# SuperLogger_widewithESPSIM800bevorroutin.net
KiCad netlist of a schematic drawn in EAGLE
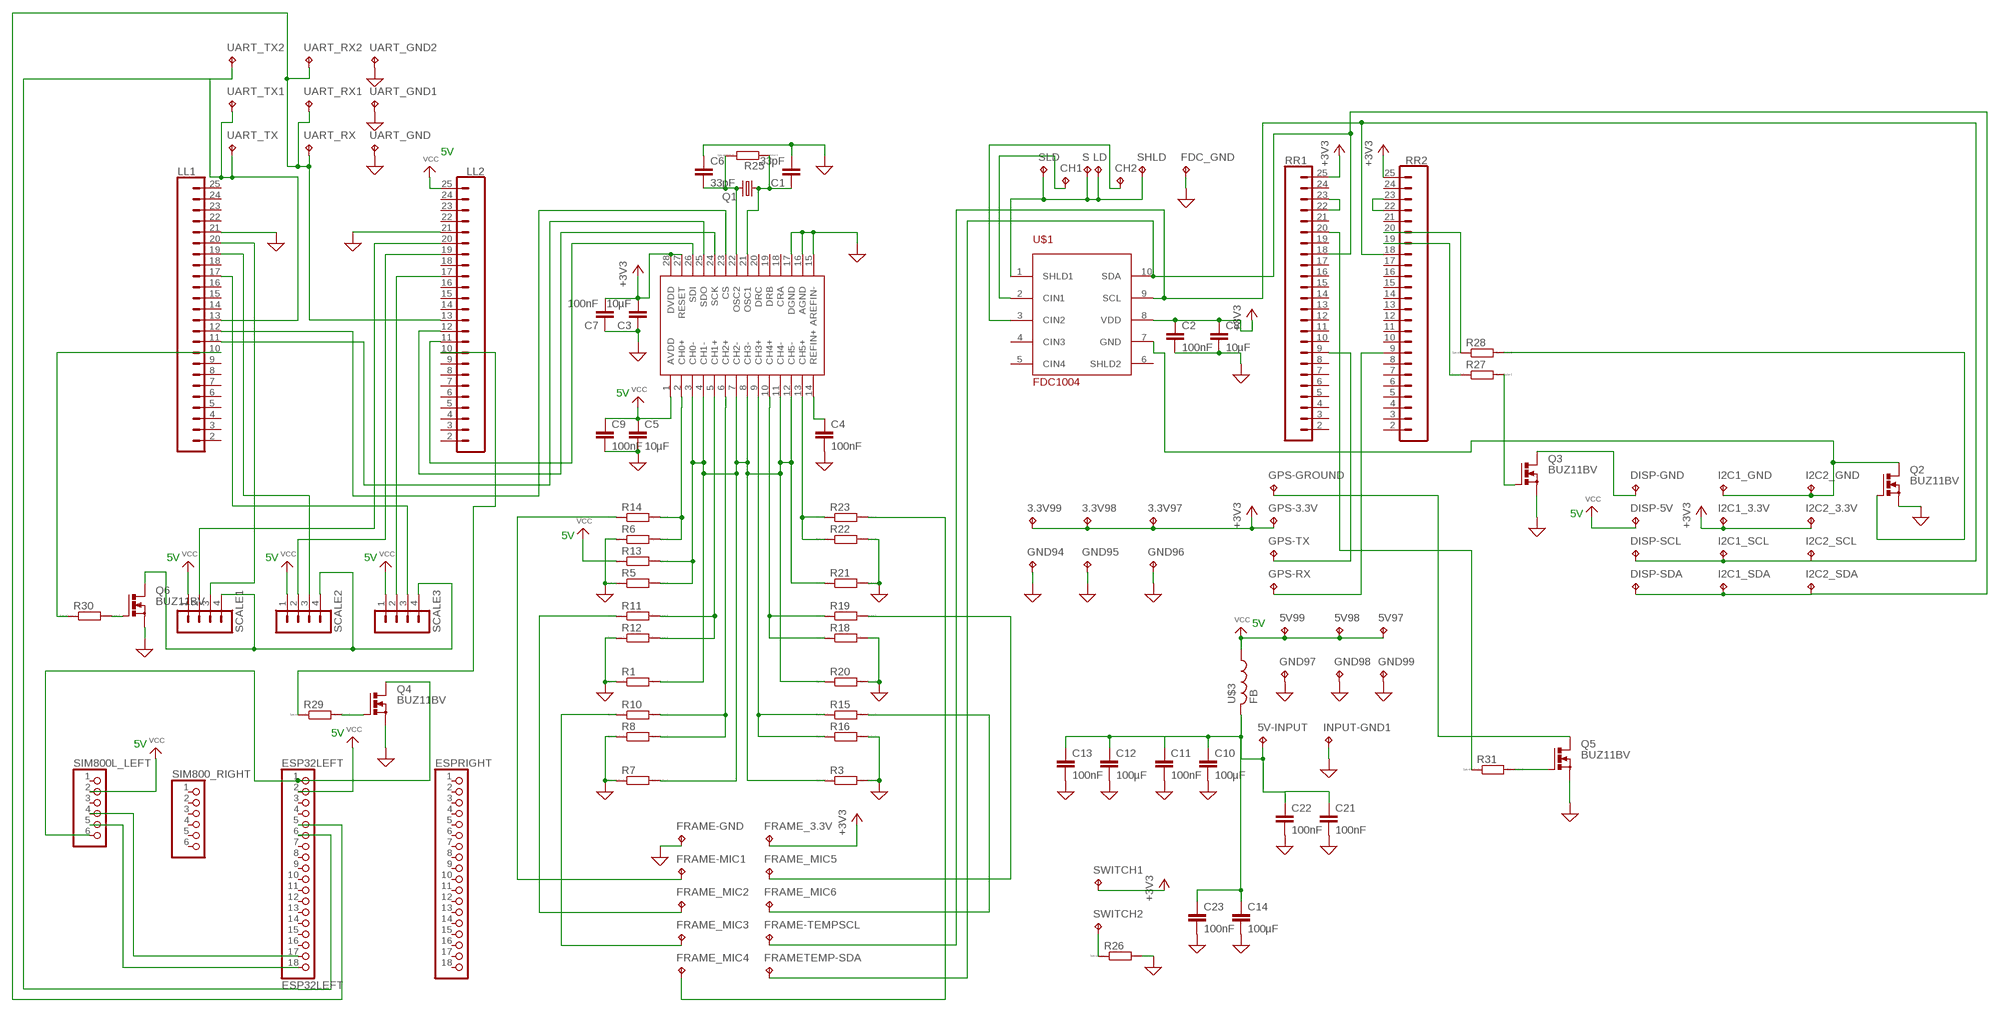
[diagram p0: schematic, sheet 1]

(export (version "E")
  (design (tool "Eeschema 10.0.6"))
  (components
    (comp (ref "3.3V97")
      (value "ground")
      (footprint "eagle-import:P1-13Y")
      (libsource (lib "eagle-import") (part "TPPAD1-13Y"))
    )
    (comp (ref "3.3V98")
      (value "ground")
      (footprint "eagle-import:P1-13Y")
      (libsource (lib "eagle-import") (part "TPPAD1-13Y"))
    )
    (comp (ref "3.3V99")
      (value "ground")
      (footprint "eagle-import:P1-13Y")
      (libsource (lib "eagle-import") (part "TPPAD1-13Y"))
    )
    (comp (ref "5V-INPUT")
      (value "ground")
      (footprint "eagle-import:P1-13Y")
      (libsource (lib "eagle-import") (part "TPPAD1-13Y"))
    )
    (comp (ref "5V97")
      (value "ground")
      (footprint "eagle-import:P1-13Y")
      (libsource (lib "eagle-import") (part "TPPAD1-13Y"))
    )
    (comp (ref "5V98")
      (value "ground")
      (footprint "eagle-import:P1-13Y")
      (libsource (lib "eagle-import") (part "TPPAD1-13Y"))
    )
    (comp (ref "5V99")
      (value "ground")
      (footprint "eagle-import:P1-13Y")
      (libsource (lib "eagle-import") (part "TPPAD1-13Y"))
    )
    (comp (ref "C1")
      (value "33pF")
      (footprint "eagle-import:C5B3")
      (libsource (lib "eagle-import") (part "C5/3"))
    )
    (comp (ref "C2")
      (value "100nF")
      (footprint "eagle-import:C5B3")
      (libsource (lib "eagle-import") (part "C5/3"))
    )
    (comp (ref "C3")
      (value "10µF")
      (footprint "eagle-import:C5B3")
      (libsource (lib "eagle-import") (part "C5/3"))
    )
    (comp (ref "C4")
      (value "100nF")
      (footprint "eagle-import:C5B3")
      (libsource (lib "eagle-import") (part "C5/3"))
    )
    (comp (ref "C5")
      (value "10µF")
      (footprint "eagle-import:C5B3")
      (libsource (lib "eagle-import") (part "C5/3"))
    )
    (comp (ref "C6")
      (value "33pF")
      (footprint "eagle-import:C5B3")
      (libsource (lib "eagle-import") (part "C5/3"))
    )
    (comp (ref "C7")
      (value "100nF")
      (footprint "eagle-import:C5B3")
      (libsource (lib "eagle-import") (part "C5/3"))
    )
    (comp (ref "C8")
      (value "10µF")
      (footprint "eagle-import:C5B3")
      (libsource (lib "eagle-import") (part "C5/3"))
    )
    (comp (ref "C9")
      (value "100nF")
      (footprint "eagle-import:C5B3")
      (libsource (lib "eagle-import") (part "C5/3"))
    )
    (comp (ref "C10")
      (value "100µF")
      (footprint "eagle-import:C5B3")
      (libsource (lib "eagle-import") (part "C5/3"))
    )
    (comp (ref "C11")
      (value "100nF")
      (footprint "eagle-import:C5B3")
      (libsource (lib "eagle-import") (part "C5/3"))
    )
    (comp (ref "C12")
      (value "100µF")
      (footprint "eagle-import:C5B3")
      (libsource (lib "eagle-import") (part "C5/3"))
    )
    (comp (ref "C13")
      (value "100nF")
      (footprint "eagle-import:C5B3")
      (libsource (lib "eagle-import") (part "C5/3"))
    )
    (comp (ref "C14")
      (value "100µF")
      (footprint "eagle-import:C5B3")
      (libsource (lib "eagle-import") (part "C5/3"))
    )
    (comp (ref "C21")
      (value "100nF")
      (footprint "eagle-import:C5B3")
      (libsource (lib "eagle-import") (part "C5/3"))
    )
    (comp (ref "C22")
      (value "100nF")
      (footprint "eagle-import:C5B3")
      (libsource (lib "eagle-import") (part "C5/3"))
    )
    (comp (ref "C23")
      (value "100nF")
      (footprint "eagle-import:C5B3")
      (libsource (lib "eagle-import") (part "C5/3"))
    )
    (comp (ref "CH1")
      (value "ground")
      (footprint "eagle-import:P1-13Y")
      (libsource (lib "eagle-import") (part "TPPAD1-13Y"))
    )
    (comp (ref "CH2")
      (value "ground")
      (footprint "eagle-import:P1-13Y")
      (libsource (lib "eagle-import") (part "TPPAD1-13Y"))
    )
    (comp (ref "DISP-5V")
      (value "ground")
      (footprint "eagle-import:P1-13Y")
      (libsource (lib "eagle-import") (part "TPPAD1-13Y"))
    )
    (comp (ref "DISP-GND")
      (value "ground")
      (footprint "eagle-import:P1-13Y")
      (libsource (lib "eagle-import") (part "TPPAD1-13Y"))
    )
    (comp (ref "DISP-SCL")
      (value "ground")
      (footprint "eagle-import:P1-13Y")
      (libsource (lib "eagle-import") (part "TPPAD1-13Y"))
    )
    (comp (ref "DISP-SDA")
      (value "ground")
      (footprint "eagle-import:P1-13Y")
      (libsource (lib "eagle-import") (part "TPPAD1-13Y"))
    )
    (comp (ref "ESP32LEFT")
      (value "ESP32LEFT")
      (footprint "eagle-import:1X18-BIG")
      (libsource (lib "eagle-import") (part "PINHD-1X18-BIG"))
    )
    (comp (ref "ESPRIGHT")
      (value "PINHD-1X18-BIG")
      (footprint "eagle-import:1X18-BIG")
      (libsource (lib "eagle-import") (part "PINHD-1X18-BIG"))
    )
    (comp (ref "FDC_GND")
      (value "ground")
      (footprint "eagle-import:P1-13Y")
      (libsource (lib "eagle-import") (part "TPPAD1-13Y"))
    )
    (comp (ref "FRAME-GND")
      (value "ground")
      (footprint "eagle-import:P1-13Y")
      (libsource (lib "eagle-import") (part "TPPAD1-13Y"))
    )
    (comp (ref "FRAME-MIC1")
      (value "ground")
      (footprint "eagle-import:P1-13Y")
      (libsource (lib "eagle-import") (part "TPPAD1-13Y"))
    )
    (comp (ref "FRAME-TEMPSCL")
      (value "ground")
      (footprint "eagle-import:P1-13Y")
      (libsource (lib "eagle-import") (part "TPPAD1-13Y"))
    )
    (comp (ref "FRAMETEMP-SDA")
      (value "ground")
      (footprint "eagle-import:P1-13Y")
      (libsource (lib "eagle-import") (part "TPPAD1-13Y"))
    )
    (comp (ref "FRAME_3.3V")
      (value "ground")
      (footprint "eagle-import:P1-13Y")
      (libsource (lib "eagle-import") (part "TPPAD1-13Y"))
    )
    (comp (ref "FRAME_MIC2")
      (value "ground")
      (footprint "eagle-import:P1-13Y")
      (libsource (lib "eagle-import") (part "TPPAD1-13Y"))
    )
    (comp (ref "FRAME_MIC3")
      (value "ground")
      (footprint "eagle-import:P1-13Y")
      (libsource (lib "eagle-import") (part "TPPAD1-13Y"))
    )
    (comp (ref "FRAME_MIC4")
      (value "ground")
      (footprint "eagle-import:P1-13Y")
      (libsource (lib "eagle-import") (part "TPPAD1-13Y"))
    )
    (comp (ref "FRAME_MIC5")
      (value "ground")
      (footprint "eagle-import:P1-13Y")
      (libsource (lib "eagle-import") (part "TPPAD1-13Y"))
    )
    (comp (ref "FRAME_MIC6")
      (value "ground")
      (footprint "eagle-import:P1-13Y")
      (libsource (lib "eagle-import") (part "TPPAD1-13Y"))
    )
    (comp (ref "GND94")
      (value "ground")
      (footprint "eagle-import:P1-13Y")
      (libsource (lib "eagle-import") (part "TPPAD1-13Y"))
    )
    (comp (ref "GND95")
      (value "ground")
      (footprint "eagle-import:P1-13Y")
      (libsource (lib "eagle-import") (part "TPPAD1-13Y"))
    )
    (comp (ref "GND96")
      (value "ground")
      (footprint "eagle-import:P1-13Y")
      (libsource (lib "eagle-import") (part "TPPAD1-13Y"))
    )
    (comp (ref "GND97")
      (value "ground")
      (footprint "eagle-import:P1-13Y")
      (libsource (lib "eagle-import") (part "TPPAD1-13Y"))
    )
    (comp (ref "GND98")
      (value "ground")
      (footprint "eagle-import:P1-13Y")
      (libsource (lib "eagle-import") (part "TPPAD1-13Y"))
    )
    (comp (ref "GND99")
      (value "ground")
      (footprint "eagle-import:P1-13Y")
      (libsource (lib "eagle-import") (part "TPPAD1-13Y"))
    )
    (comp (ref "GPS-3.3V")
      (value "ground")
      (footprint "eagle-import:P1-13Y")
      (libsource (lib "eagle-import") (part "TPPAD1-13Y"))
    )
    (comp (ref "GPS-GROUND")
      (value "ground")
      (footprint "eagle-import:P1-13Y")
      (libsource (lib "eagle-import") (part "TPPAD1-13Y"))
    )
    (comp (ref "GPS-RX")
      (value "ground")
      (footprint "eagle-import:P1-13Y")
      (libsource (lib "eagle-import") (part "TPPAD1-13Y"))
    )
    (comp (ref "GPS-TX")
      (value "ground")
      (footprint "eagle-import:P1-13Y")
      (libsource (lib "eagle-import") (part "TPPAD1-13Y"))
    )
    (comp (ref "I2C1_3.3V")
      (value "ground")
      (footprint "eagle-import:P1-13Y")
      (libsource (lib "eagle-import") (part "TPPAD1-13Y"))
    )
    (comp (ref "I2C1_GND")
      (value "ground")
      (footprint "eagle-import:P1-13Y")
      (libsource (lib "eagle-import") (part "TPPAD1-13Y"))
    )
    (comp (ref "I2C1_SCL")
      (value "ground")
      (footprint "eagle-import:P1-13Y")
      (libsource (lib "eagle-import") (part "TPPAD1-13Y"))
    )
    (comp (ref "I2C1_SDA")
      (value "ground")
      (footprint "eagle-import:P1-13Y")
      (libsource (lib "eagle-import") (part "TPPAD1-13Y"))
    )
    (comp (ref "I2C2_3.3V")
      (value "ground")
      (footprint "eagle-import:P1-13Y")
      (libsource (lib "eagle-import") (part "TPPAD1-13Y"))
    )
    (comp (ref "I2C2_GND")
      (value "ground")
      (footprint "eagle-import:P1-13Y")
      (libsource (lib "eagle-import") (part "TPPAD1-13Y"))
    )
    (comp (ref "I2C2_SCL")
      (value "ground")
      (footprint "eagle-import:P1-13Y")
      (libsource (lib "eagle-import") (part "TPPAD1-13Y"))
    )
    (comp (ref "I2C2_SDA")
      (value "ground")
      (footprint "eagle-import:P1-13Y")
      (libsource (lib "eagle-import") (part "TPPAD1-13Y"))
    )
    (comp (ref "INPUT-GND1")
      (value "ground")
      (footprint "eagle-import:P1-13Y")
      (libsource (lib "eagle-import") (part "TPPAD1-13Y"))
    )
    (comp (ref "LD")
      (value "ground")
      (footprint "eagle-import:P1-13Y")
      (libsource (lib "eagle-import") (part "TPPAD1-13Y"))
    )
    (comp (ref "LL1")
      (value "CONN_24")
      (footprint "eagle-import:1X24")
      (libsource (lib "eagle-import") (part "CONN_24"))
    )
    (comp (ref "LL2")
      (value "CONN_24")
      (footprint "eagle-import:1X24")
      (libsource (lib "eagle-import") (part "CONN_24"))
    )
    (comp (ref "Q1")
      (value "CRYSTALHC49S")
      (footprint "eagle-import:HC49_S")
      (libsource (lib "eagle-import") (part "CRYSTALHC49S"))
    )
    (comp (ref "Q2")
      (value "BUZ11BV")
      (footprint "eagle-import:TO220BV")
      (libsource (lib "eagle-import") (part "BUZ11BV"))
    )
    (comp (ref "Q3")
      (value "BUZ11BV")
      (footprint "eagle-import:TO220BV")
      (libsource (lib "eagle-import") (part "BUZ11BV"))
    )
    (comp (ref "Q4")
      (value "BUZ11BV")
      (footprint "eagle-import:TO220BV")
      (libsource (lib "eagle-import") (part "BUZ11BV"))
    )
    (comp (ref "Q5")
      (value "BUZ11BV")
      (footprint "eagle-import:TO220BV")
      (libsource (lib "eagle-import") (part "BUZ11BV"))
    )
    (comp (ref "Q6")
      (value "BUZ11BV")
      (footprint "eagle-import:TO220BV")
      (libsource (lib "eagle-import") (part "BUZ11BV"))
    )
    (comp (ref "R1")
      (value "R0207/10")
      (footprint "eagle-import:0207_10")
      (libsource (lib "eagle-import") (part "R0207/10"))
    )
    (comp (ref "R3")
      (value "R0207/10")
      (footprint "eagle-import:0207_10")
      (libsource (lib "eagle-import") (part "R0207/10"))
    )
    (comp (ref "R5")
      (value "R0207/10")
      (footprint "eagle-import:0207_10")
      (libsource (lib "eagle-import") (part "R0207/10"))
    )
    (comp (ref "R6")
      (value "R0207/10")
      (footprint "eagle-import:0207_10")
      (libsource (lib "eagle-import") (part "R0207/10"))
    )
    (comp (ref "R7")
      (value "R0207/10")
      (footprint "eagle-import:0207_10")
      (libsource (lib "eagle-import") (part "R0207/10"))
    )
    (comp (ref "R8")
      (value "R0207/10")
      (footprint "eagle-import:0207_10")
      (libsource (lib "eagle-import") (part "R0207/10"))
    )
    (comp (ref "R10")
      (value "R0207/10")
      (footprint "eagle-import:0207_10")
      (libsource (lib "eagle-import") (part "R0207/10"))
    )
    (comp (ref "R11")
      (value "R0207/10")
      (footprint "eagle-import:0207_10")
      (libsource (lib "eagle-import") (part "R0207/10"))
    )
    (comp (ref "R12")
      (value "R0207/10")
      (footprint "eagle-import:0207_10")
      (libsource (lib "eagle-import") (part "R0207/10"))
    )
    (comp (ref "R13")
      (value "R0207/10")
      (footprint "eagle-import:0207_10")
      (libsource (lib "eagle-import") (part "R0207/10"))
    )
    (comp (ref "R14")
      (value "R0207/10")
      (footprint "eagle-import:0207_10")
      (libsource (lib "eagle-import") (part "R0207/10"))
    )
    (comp (ref "R15")
      (value "R0207/10")
      (footprint "eagle-import:0207_10")
      (libsource (lib "eagle-import") (part "R0207/10"))
    )
    (comp (ref "R16")
      (value "R0207/10")
      (footprint "eagle-import:0207_10")
      (libsource (lib "eagle-import") (part "R0207/10"))
    )
    (comp (ref "R18")
      (value "R0207/10")
      (footprint "eagle-import:0207_10")
      (libsource (lib "eagle-import") (part "R0207/10"))
    )
    (comp (ref "R19")
      (value "R0207/10")
      (footprint "eagle-import:0207_10")
      (libsource (lib "eagle-import") (part "R0207/10"))
    )
    (comp (ref "R20")
      (value "R0207/10")
      (footprint "eagle-import:0207_10")
      (libsource (lib "eagle-import") (part "R0207/10"))
    )
    (comp (ref "R21")
      (value "R0207/10")
      (footprint "eagle-import:0207_10")
      (libsource (lib "eagle-import") (part "R0207/10"))
    )
    (comp (ref "R22")
      (value "R0207/10")
      (footprint "eagle-import:0207_10")
      (libsource (lib "eagle-import") (part "R0207/10"))
    )
    (comp (ref "R23")
      (value "R0207/10")
      (footprint "eagle-import:0207_10")
      (libsource (lib "eagle-import") (part "R0207/10"))
    )
    (comp (ref "R25")
      (value "R0207/10")
      (footprint "eagle-import:0207_10")
      (libsource (lib "eagle-import") (part "R0207/10"))
    )
    (comp (ref "R26")
      (value "R0207/10")
      (footprint "eagle-import:0207_10")
      (libsource (lib "eagle-import") (part "R0207/10"))
    )
    (comp (ref "R27")
      (value "R0207/10")
      (footprint "eagle-import:0207_10")
      (libsource (lib "eagle-import") (part "R0207/10"))
    )
    (comp (ref "R28")
      (value "R0207/10")
      (footprint "eagle-import:0207_10")
      (libsource (lib "eagle-import") (part "R0207/10"))
    )
    (comp (ref "R29")
      (value "R0207/10")
      (footprint "eagle-import:0207_10")
      (libsource (lib "eagle-import") (part "R0207/10"))
    )
    (comp (ref "R30")
      (value "R0207/10")
      (footprint "eagle-import:0207_10")
      (libsource (lib "eagle-import") (part "R0207/10"))
    )
    (comp (ref "R31")
      (value "R0207/10")
      (footprint "eagle-import:0207_10")
      (libsource (lib "eagle-import") (part "R0207/10"))
    )
    (comp (ref "RR1")
      (value "CONN_24")
      (footprint "eagle-import:1X24")
      (libsource (lib "eagle-import") (part "CONN_24"))
    )
    (comp (ref "RR2")
      (value "CONN_24")
      (footprint "eagle-import:1X24")
      (libsource (lib "eagle-import") (part "CONN_24"))
    )
    (comp (ref "S")
      (value "ground")
      (footprint "eagle-import:P1-13Y")
      (libsource (lib "eagle-import") (part "TPPAD1-13Y"))
    )
    (comp (ref "SCALE1")
      (value "MA04-1")
      (footprint "eagle-import:MA04-1")
      (libsource (lib "eagle-import") (part "MA04-1"))
    )
    (comp (ref "SCALE2")
      (value "MA04-1")
      (footprint "eagle-import:MA04-1")
      (libsource (lib "eagle-import") (part "MA04-1"))
    )
    (comp (ref "SCALE3")
      (value "MA04-1")
      (footprint "eagle-import:MA04-1")
      (libsource (lib "eagle-import") (part "MA04-1"))
    )
    (comp (ref "SHLD")
      (value "ground")
      (footprint "eagle-import:P1-13Y")
      (libsource (lib "eagle-import") (part "TPPAD1-13Y"))
    )
    (comp (ref "SIM800L_LEFT")
      (value "PINHD-1X6")
      (footprint "eagle-import:1X06")
      (libsource (lib "eagle-import") (part "PINHD-1X6"))
    )
    (comp (ref "SIM800_RIGHT")
      (value "PINHD-1X6")
      (footprint "eagle-import:1X06")
      (libsource (lib "eagle-import") (part "PINHD-1X6"))
    )
    (comp (ref "SLD")
      (value "ground")
      (footprint "eagle-import:P1-13Y")
      (libsource (lib "eagle-import") (part "TPPAD1-13Y"))
    )
    (comp (ref "SWITCH1")
      (value "ground")
      (footprint "eagle-import:P1-13Y")
      (libsource (lib "eagle-import") (part "TPPAD1-13Y"))
    )
    (comp (ref "SWITCH2")
      (value "ground")
      (footprint "eagle-import:P1-13Y")
      (libsource (lib "eagle-import") (part "TPPAD1-13Y"))
    )
    (comp (ref "U$1")
      (value "FDC1004")
      (footprint "eagle-import:MSOP10")
      (libsource (lib "eagle-import") (part "FDC1004"))
    )
    (comp (ref "U$2")
      (value "MCP3903")
      (footprint "eagle-import:MSOP8_0.65MM")
      (libsource (lib "eagle-import") (part "MCP3903"))
    )
    (comp (ref "U$3") (value "FB") (footprint "eagle-import:FB") (libsource (lib "eagle-import") (part "FB")))
    (comp (ref "UART_GND")
      (value "ground")
      (footprint "eagle-import:P1-13Y")
      (libsource (lib "eagle-import") (part "TPPAD1-13Y"))
    )
    (comp (ref "UART_GND1")
      (value "ground")
      (footprint "eagle-import:P1-13Y")
      (libsource (lib "eagle-import") (part "TPPAD1-13Y"))
    )
    (comp (ref "UART_GND2")
      (value "ground")
      (footprint "eagle-import:P1-13Y")
      (libsource (lib "eagle-import") (part "TPPAD1-13Y"))
    )
    (comp (ref "UART_RX")
      (value "ground")
      (footprint "eagle-import:P1-13Y")
      (libsource (lib "eagle-import") (part "TPPAD1-13Y"))
    )
    (comp (ref "UART_RX1")
      (value "ground")
      (footprint "eagle-import:P1-13Y")
      (libsource (lib "eagle-import") (part "TPPAD1-13Y"))
    )
    (comp (ref "UART_RX2")
      (value "ground")
      (footprint "eagle-import:P1-13Y")
      (libsource (lib "eagle-import") (part "TPPAD1-13Y"))
    )
    (comp (ref "UART_TX")
      (value "ground")
      (footprint "eagle-import:P1-13Y")
      (libsource (lib "eagle-import") (part "TPPAD1-13Y"))
    )
    (comp (ref "UART_TX1")
      (value "ground")
      (footprint "eagle-import:P1-13Y")
      (libsource (lib "eagle-import") (part "TPPAD1-13Y"))
    )
    (comp (ref "UART_TX2")
      (value "ground")
      (footprint "eagle-import:P1-13Y")
      (libsource (lib "eagle-import") (part "TPPAD1-13Y"))
    )
  )
  (nets
    (net (code "1") (name "+3V3") (class "Default")
      (node (ref "3.3V97") (pin "TP") (pinfunction "TP_TP") (pintype "input"))
      (node (ref "3.3V98") (pin "TP") (pinfunction "TP_TP") (pintype "input"))
      (node (ref "3.3V99") (pin "TP") (pinfunction "TP_TP") (pintype "input"))
      (node (ref "C2") (pin "1") (pinfunction "1_1") (pintype "passive"))
      (node (ref "C3") (pin "2") (pinfunction "2_2") (pintype "passive"))
      (node (ref "C7") (pin "2") (pinfunction "2_2") (pintype "passive"))
      (node (ref "C8") (pin "1") (pinfunction "1_1") (pintype "passive"))
      (node (ref "FRAME_3.3V") (pin "TP") (pinfunction "TP_TP") (pintype "input"))
      (node (ref "GPS-3.3V") (pin "TP") (pinfunction "TP_TP") (pintype "input"))
      (node (ref "I2C1_3.3V") (pin "TP") (pinfunction "TP_TP") (pintype "input"))
      (node (ref "I2C2_3.3V") (pin "TP") (pinfunction "TP_TP") (pintype "input"))
      (node (ref "RR1") (pin "25") (pinfunction "25_25") (pintype "passive"))
      (node (ref "RR2") (pin "25") (pinfunction "25_25") (pintype "passive"))
      (node (ref "SWITCH1") (pin "TP") (pinfunction "TP_TP") (pintype "input"))
      (node (ref "U$1") (pin "8") (pinfunction "VDD_8") (pintype "power_in"))
      (node (ref "U$2") (pin "27") (pinfunction "RESET_27") (pintype "output"))
      (node (ref "U$2") (pin "28") (pinfunction "DVDD_28") (pintype "output"))
    )
    (net (code "2") (name "Net-(DISP-GND-PadTP)") (class "Default")
      (node (ref "DISP-GND") (pin "TP") (pinfunction "TP_TP") (pintype "input"))
      (node (ref "Q3") (pin "D") (pinfunction "D_D") (pintype "passive"))
    )
    (net (code "3") (name "Net-(ESP32LEFT-Pad1)") (class "Default")
      (node (ref "ESP32LEFT") (pin "1") (pinfunction "1_1") (pintype "passive"))
      (node (ref "Q4") (pin "D") (pinfunction "D_D") (pintype "passive"))
      (node (ref "SIM800L_LEFT") (pin "6") (pinfunction "6_6") (pintype "passive"))
    )
    (net (code "4") (name "Net-(ESP32LEFT-Pad5)") (class "Default")
      (node (ref "ESP32LEFT") (pin "5") (pinfunction "5_5") (pintype "passive"))
      (node (ref "LL2") (pin "13") (pinfunction "13_13") (pintype "passive"))
      (node (ref "UART_RX") (pin "TP") (pinfunction "TP_TP") (pintype "input"))
      (node (ref "UART_RX1") (pin "TP") (pinfunction "TP_TP") (pintype "input"))
      (node (ref "UART_RX2") (pin "TP") (pinfunction "TP_TP") (pintype "input"))
    )
    (net (code "5") (name "Net-(ESP32LEFT-Pad6)") (class "Default")
      (node (ref "ESP32LEFT") (pin "6") (pinfunction "6_6") (pintype "passive"))
      (node (ref "LL1") (pin "13") (pinfunction "13_13") (pintype "passive"))
      (node (ref "UART_TX") (pin "TP") (pinfunction "TP_TP") (pintype "input"))
      (node (ref "UART_TX1") (pin "TP") (pinfunction "TP_TP") (pintype "input"))
      (node (ref "UART_TX2") (pin "TP") (pinfunction "TP_TP") (pintype "input"))
    )
    (net (code "6") (name "Net-(ESP32LEFT-Pad17)") (class "Default")
      (node (ref "ESP32LEFT") (pin "17") (pinfunction "17_17") (pintype "passive"))
      (node (ref "SIM800L_LEFT") (pin "4") (pinfunction "4_4") (pintype "passive"))
    )
    (net (code "7") (name "Net-(ESP32LEFT-Pad18)") (class "Default")
      (node (ref "ESP32LEFT") (pin "18") (pinfunction "18_18") (pintype "passive"))
      (node (ref "SIM800L_LEFT") (pin "5") (pinfunction "5_5") (pintype "passive"))
    )
    (net (code "8") (name "Net-(FRAME-MIC1-PadTP)") (class "Default")
      (node (ref "FRAME-MIC1") (pin "TP") (pinfunction "TP_TP") (pintype "input"))
      (node (ref "R14") (pin "1") (pinfunction "1_1") (pintype "passive"))
    )
    (net (code "9") (name "Net-(FRAME_MIC2-PadTP)") (class "Default")
      (node (ref "FRAME_MIC2") (pin "TP") (pinfunction "TP_TP") (pintype "input"))
      (node (ref "R11") (pin "1") (pinfunction "1_1") (pintype "passive"))
    )
    (net (code "10") (name "Net-(FRAME_MIC3-PadTP)") (class "Default")
      (node (ref "FRAME_MIC3") (pin "TP") (pinfunction "TP_TP") (pintype "input"))
      (node (ref "R10") (pin "1") (pinfunction "1_1") (pintype "passive"))
    )
    (net (code "11") (name "Net-(FRAME_MIC4-PadTP)") (class "Default")
      (node (ref "FRAME_MIC4") (pin "TP") (pinfunction "TP_TP") (pintype "input"))
      (node (ref "R23") (pin "2") (pinfunction "2_2") (pintype "passive"))
    )
    (net (code "12") (name "Net-(FRAME_MIC5-PadTP)") (class "Default")
      (node (ref "FRAME_MIC5") (pin "TP") (pinfunction "TP_TP") (pintype "input"))
      (node (ref "R19") (pin "2") (pinfunction "2_2") (pintype "passive"))
    )
    (net (code "13") (name "Net-(FRAME_MIC6-PadTP)") (class "Default")
      (node (ref "FRAME_MIC6") (pin "TP") (pinfunction "TP_TP") (pintype "input"))
      (node (ref "R15") (pin "2") (pinfunction "2_2") (pintype "passive"))
    )
    (net (code "14") (name "Net-(GPS-GROUND-PadTP)") (class "Default")
      (node (ref "GPS-GROUND") (pin "TP") (pinfunction "TP_TP") (pintype "input"))
      (node (ref "Q5") (pin "D") (pinfunction "D_D") (pintype "passive"))
    )
    (net (code "15") (name "Net-(GPS-RX-PadTP)") (class "Default")
      (node (ref "GPS-RX") (pin "TP") (pinfunction "TP_TP") (pintype "input"))
      (node (ref "RR2") (pin "9") (pinfunction "9_9") (pintype "passive"))
    )
    (net (code "16") (name "Net-(GPS-TX-PadTP)") (class "Default")
      (node (ref "GPS-TX") (pin "TP") (pinfunction "TP_TP") (pintype "input"))
      (node (ref "RR1") (pin "9") (pinfunction "9_9") (pintype "passive"))
    )
    (net (code "17") (name "Net-(LL1-Pad10)") (class "Default")
      (node (ref "LL1") (pin "10") (pinfunction "10_10") (pintype "passive"))
      (node (ref "R30") (pin "1") (pinfunction "1_1") (pintype "passive"))
    )
    (net (code "18") (name "Net-(LL1-Pad17)") (class "Default")
      (node (ref "LL1") (pin "17") (pinfunction "17_17") (pintype "passive"))
      (node (ref "SCALE3") (pin "3") (pinfunction "3_3") (pintype "passive"))
    )
    (net (code "19") (name "Net-(LL1-Pad19)") (class "Default")
      (node (ref "LL1") (pin "19") (pinfunction "19_19") (pintype "passive"))
      (node (ref "SCALE2") (pin "3") (pinfunction "3_3") (pintype "passive"))
    )
    (net (code "20") (name "Net-(LL1-Pad20)") (class "Default")
      (node (ref "LL1") (pin "20") (pinfunction "20_20") (pintype "passive"))
      (node (ref "SCALE1") (pin "3") (pinfunction "3_3") (pintype "passive"))
    )
    (net (code "21") (name "Net-(LL2-Pad10)") (class "Default")
      (node (ref "LL2") (pin "10") (pinfunction "10_10") (pintype "passive"))
      (node (ref "R29") (pin "1") (pinfunction "1_1") (pintype "passive"))
    )
    (net (code "22") (name "Net-(LL2-Pad17)") (class "Default")
      (node (ref "LL2") (pin "17") (pinfunction "17_17") (pintype "passive"))
      (node (ref "SCALE3") (pin "2") (pinfunction "2_2") (pintype "passive"))
    )
    (net (code "23") (name "Net-(LL2-Pad19)") (class "Default")
      (node (ref "LL2") (pin "19") (pinfunction "19_19") (pintype "passive"))
      (node (ref "SCALE2") (pin "2") (pinfunction "2_2") (pintype "passive"))
    )
    (net (code "24") (name "Net-(LL2-Pad20)") (class "Default")
      (node (ref "LL2") (pin "20") (pinfunction "20_20") (pintype "passive"))
      (node (ref "SCALE1") (pin "2") (pinfunction "2_2") (pintype "passive"))
    )
    (net (code "25") (name "Net-(Q2-PadG)") (class "Default")
      (node (ref "Q2") (pin "G") (pinfunction "G_G") (pintype "passive"))
      (node (ref "R28") (pin "2") (pinfunction "2_2") (pintype "passive"))
    )
    (net (code "26") (name "Net-(Q3-PadG)") (class "Default")
      (node (ref "Q3") (pin "G") (pinfunction "G_G") (pintype "passive"))
      (node (ref "R27") (pin "2") (pinfunction "2_2") (pintype "passive"))
    )
    (net (code "27") (name "Net-(Q4-PadG)") (class "Default")
      (node (ref "Q4") (pin "G") (pinfunction "G_G") (pintype "passive"))
      (node (ref "R29") (pin "2") (pinfunction "2_2") (pintype "passive"))
    )
    (net (code "28") (name "Net-(Q5-PadG)") (class "Default")
      (node (ref "Q5") (pin "G") (pinfunction "G_G") (pintype "passive"))
      (node (ref "R31") (pin "2") (pinfunction "2_2") (pintype "passive"))
    )
    (net (code "29") (name "Net-(Q6-PadD)") (class "Default")
      (node (ref "Q6") (pin "D") (pinfunction "D_D") (pintype "passive"))
      (node (ref "SCALE1") (pin "4") (pinfunction "4_4") (pintype "passive"))
      (node (ref "SCALE2") (pin "4") (pinfunction "4_4") (pintype "passive"))
      (node (ref "SCALE3") (pin "4") (pinfunction "4_4") (pintype "passive"))
    )
    (net (code "30") (name "Net-(Q6-PadG)") (class "Default")
      (node (ref "Q6") (pin "G") (pinfunction "G_G") (pintype "passive"))
      (node (ref "R30") (pin "2") (pinfunction "2_2") (pintype "passive"))
    )
    (net (code "31") (name "Net-(R26-Pad1)") (class "Default")
      (node (ref "R26") (pin "1") (pinfunction "1_1") (pintype "passive"))
      (node (ref "SWITCH2") (pin "TP") (pinfunction "TP_TP") (pintype "input"))
    )
    (net (code "32") (name "Net-(R27-Pad1)") (class "Default")
      (node (ref "R27") (pin "1") (pinfunction "1_1") (pintype "passive"))
      (node (ref "RR2") (pin "19") (pinfunction "19_19") (pintype "passive"))
    )
    (net (code "33") (name "Net-(R28-Pad1)") (class "Default")
      (node (ref "R28") (pin "1") (pinfunction "1_1") (pintype "passive"))
      (node (ref "RR2") (pin "20") (pinfunction "20_20") (pintype "passive"))
    )
    (net (code "34") (name "Net-(R31-Pad1)") (class "Default")
      (node (ref "R31") (pin "1") (pinfunction "1_1") (pintype "passive"))
      (node (ref "RR1") (pin "20") (pinfunction "20_20") (pintype "passive"))
    )
    (net (code "35") (name "Net-(RR1-Pad22)") (class "Default")
      (node (ref "RR1") (pin "22") (pinfunction "22_22") (pintype "passive"))
      (node (ref "RR1") (pin "23") (pinfunction "23_23") (pintype "passive"))
    )
    (net (code "36") (name "Net-(RR2-Pad22)") (class "Default")
      (node (ref "RR2") (pin "22") (pinfunction "22_22") (pintype "passive"))
      (node (ref "RR2") (pin "23") (pinfunction "23_23") (pintype "passive"))
    )
    (net (code "37") (name "Net-(U$1-CIN1)") (class "Default")
      (node (ref "CH1") (pin "TP") (pinfunction "TP_TP") (pintype "input"))
      (node (ref "U$1") (pin "2") (pinfunction "CIN1_2") (pintype "input"))
    )
    (net (code "38") (name "Net-(U$1-CIN2)") (class "Default")
      (node (ref "CH2") (pin "TP") (pinfunction "TP_TP") (pintype "input"))
      (node (ref "U$1") (pin "3") (pinfunction "CIN2_3") (pintype "input"))
    )
    (net (code "39") (name "Net-(U$1-GND)") (class "Default")
      (node (ref "I2C1_GND") (pin "TP") (pinfunction "TP_TP") (pintype "input"))
      (node (ref "I2C2_GND") (pin "TP") (pinfunction "TP_TP") (pintype "input"))
      (node (ref "Q2") (pin "D") (pinfunction "D_D") (pintype "passive"))
      (node (ref "U$1") (pin "7") (pinfunction "GND_7") (pintype "power_in"))
    )
    (net (code "40") (name "Net-(U$1-SCL)") (class "Default")
      (node (ref "DISP-SCL") (pin "TP") (pinfunction "TP_TP") (pintype "input"))
      (node (ref "FRAME-TEMPSCL") (pin "TP") (pinfunction "TP_TP") (pintype "input"))
      (node (ref "I2C1_SCL") (pin "TP") (pinfunction "TP_TP") (pintype "input"))
      (node (ref "I2C2_SCL") (pin "TP") (pinfunction "TP_TP") (pintype "input"))
      (node (ref "RR2") (pin "18") (pinfunction "18_18") (pintype "passive"))
      (node (ref "U$1") (pin "9") (pinfunction "SCL_9") (pintype "bidirectional"))
    )
    (net (code "41") (name "Net-(U$1-SDA)") (class "Default")
      (node (ref "DISP-SDA") (pin "TP") (pinfunction "TP_TP") (pintype "input"))
      (node (ref "FRAMETEMP-SDA") (pin "TP") (pinfunction "TP_TP") (pintype "input"))
      (node (ref "I2C1_SDA") (pin "TP") (pinfunction "TP_TP") (pintype "input"))
      (node (ref "I2C2_SDA") (pin "TP") (pinfunction "TP_TP") (pintype "input"))
      (node (ref "RR1") (pin "18") (pinfunction "18_18") (pintype "passive"))
      (node (ref "U$1") (pin "10") (pinfunction "SDA_10") (pintype "bidirectional"))
    )
    (net (code "42") (name "Net-(U$1-SHLD1)") (class "Default")
      (node (ref "LD") (pin "TP") (pinfunction "TP_TP") (pintype "input"))
      (node (ref "S") (pin "TP") (pinfunction "TP_TP") (pintype "input"))
      (node (ref "SHLD") (pin "TP") (pinfunction "TP_TP") (pintype "input"))
      (node (ref "SLD") (pin "TP") (pinfunction "TP_TP") (pintype "input"))
      (node (ref "U$1") (pin "1") (pinfunction "SHLD1_1") (pintype "output"))
    )
    (net (code "43") (name "Net-(U$2-CH0+)") (class "Default")
      (node (ref "R14") (pin "2") (pinfunction "2_2") (pintype "passive"))
      (node (ref "R6") (pin "2") (pinfunction "2_2") (pintype "passive"))
      (node (ref "U$2") (pin "2") (pinfunction "CH0+_2") (pintype "output"))
    )
    (net (code "44") (name "Net-(U$2-CH0-)") (class "Default")
      (node (ref "R1") (pin "2") (pinfunction "2_2") (pintype "passive"))
      (node (ref "R13") (pin "2") (pinfunction "2_2") (pintype "passive"))
      (node (ref "R20") (pin "1") (pinfunction "1_1") (pintype "passive"))
      (node (ref "R21") (pin "1") (pinfunction "1_1") (pintype "passive"))
      (node (ref "R3") (pin "1") (pinfunction "1_1") (pintype "passive"))
      (node (ref "R5") (pin "2") (pinfunction "2_2") (pintype "passive"))
      (node (ref "R7") (pin "2") (pinfunction "2_2") (pintype "passive"))
      (node (ref "U$2") (pin "11") (pinfunction "CH4-_11") (pintype "output"))
      (node (ref "U$2") (pin "12") (pinfunction "CH5-_12") (pintype "output"))
      (node (ref "U$2") (pin "3") (pinfunction "CH0-_3") (pintype "output"))
      (node (ref "U$2") (pin "4") (pinfunction "CH1-_4") (pintype "output"))
      (node (ref "U$2") (pin "7") (pinfunction "CH2-_7") (pintype "output"))
      (node (ref "U$2") (pin "8") (pinfunction "CH3-_8") (pintype "output"))
    )
    (net (code "45") (name "Net-(U$2-CH1+)") (class "Default")
      (node (ref "R11") (pin "2") (pinfunction "2_2") (pintype "passive"))
      (node (ref "R12") (pin "2") (pinfunction "2_2") (pintype "passive"))
      (node (ref "U$2") (pin "5") (pinfunction "CH1+_5") (pintype "output"))
    )
    (net (code "46") (name "Net-(U$2-CH2+)") (class "Default")
      (node (ref "R10") (pin "2") (pinfunction "2_2") (pintype "passive"))
      (node (ref "R8") (pin "2") (pinfunction "2_2") (pintype "passive"))
      (node (ref "U$2") (pin "6") (pinfunction "CH2+_6") (pintype "output"))
    )
    (net (code "47") (name "Net-(U$2-CH3+)") (class "Default")
      (node (ref "R15") (pin "1") (pinfunction "1_1") (pintype "passive"))
      (node (ref "R16") (pin "1") (pinfunction "1_1") (pintype "passive"))
      (node (ref "U$2") (pin "9") (pinfunction "CH3+_9") (pintype "output"))
    )
    (net (code "48") (name "Net-(U$2-CH4+)") (class "Default")
      (node (ref "R18") (pin "1") (pinfunction "1_1") (pintype "passive"))
      (node (ref "R19") (pin "1") (pinfunction "1_1") (pintype "passive"))
      (node (ref "U$2") (pin "10") (pinfunction "CH4+_10") (pintype "output"))
    )
    (net (code "49") (name "Net-(U$2-CH5+)") (class "Default")
      (node (ref "R22") (pin "1") (pinfunction "1_1") (pintype "passive"))
      (node (ref "R23") (pin "1") (pinfunction "1_1") (pintype "passive"))
      (node (ref "U$2") (pin "13") (pinfunction "CH5+_13") (pintype "output"))
    )
    (net (code "50") (name "Net-(U$2-CS)") (class "Default")
      (node (ref "LL1") (pin "12") (pinfunction "12_12") (pintype "passive"))
      (node (ref "U$2") (pin "23") (pinfunction "CS_23") (pintype "output"))
    )
    (net (code "51") (name "Net-(U$2-OSC1)") (class "Default")
      (node (ref "C1") (pin "1") (pinfunction "1_1") (pintype "passive"))
      (node (ref "Q1") (pin "1") (pinfunction "1_1") (pintype "passive"))
      (node (ref "R25") (pin "1") (pinfunction "1_1") (pintype "passive"))
      (node (ref "U$2") (pin "21") (pinfunction "OSC1_21") (pintype "output"))
    )
    (net (code "52") (name "Net-(U$2-OSC2)") (class "Default")
      (node (ref "C6") (pin "2") (pinfunction "2_2") (pintype "passive"))
      (node (ref "Q1") (pin "2") (pinfunction "2_2") (pintype "passive"))
      (node (ref "R25") (pin "2") (pinfunction "2_2") (pintype "passive"))
      (node (ref "U$2") (pin "22") (pinfunction "OSC2_22") (pintype "output"))
    )
    (net (code "53") (name "Net-(U$2-REFIN+)") (class "Default")
      (node (ref "C4") (pin "1") (pinfunction "1_1") (pintype "passive"))
      (node (ref "U$2") (pin "14") (pinfunction "REFIN+_14") (pintype "output"))
    )
    (net (code "54") (name "Net-(U$2-SCK)") (class "Default")
      (node (ref "LL2") (pin "12") (pinfunction "12_12") (pintype "passive"))
      (node (ref "U$2") (pin "24") (pinfunction "SCK_24") (pintype "output"))
    )
    (net (code "55") (name "Net-(U$2-SDI)") (class "Default")
      (node (ref "LL2") (pin "11") (pinfunction "11_11") (pintype "passive"))
      (node (ref "U$2") (pin "26") (pinfunction "SDI_26") (pintype "output"))
    )
    (net (code "56") (name "Net-(U$2-SDO)") (class "Default")
      (node (ref "LL1") (pin "11") (pinfunction "11_11") (pintype "passive"))
      (node (ref "U$2") (pin "25") (pinfunction "SDO_25") (pintype "output"))
    )
    (net (code "57") (name "SUP") (class "Default")
      (node (ref "C1") (pin "2") (pinfunction "2_2") (pintype "passive"))
      (node (ref "C10") (pin "2") (pinfunction "2_2") (pintype "passive"))
      (node (ref "C11") (pin "2") (pinfunction "2_2") (pintype "passive"))
      (node (ref "C12") (pin "2") (pinfunction "2_2") (pintype "passive"))
      (node (ref "C13") (pin "2") (pinfunction "2_2") (pintype "passive"))
      (node (ref "C14") (pin "2") (pinfunction "2_2") (pintype "passive"))
      (node (ref "C2") (pin "2") (pinfunction "2_2") (pintype "passive"))
      (node (ref "C21") (pin "2") (pinfunction "2_2") (pintype "passive"))
      (node (ref "C22") (pin "2") (pinfunction "2_2") (pintype "passive"))
      (node (ref "C23") (pin "2") (pinfunction "2_2") (pintype "passive"))
      (node (ref "C3") (pin "1") (pinfunction "1_1") (pintype "passive"))
      (node (ref "C4") (pin "2") (pinfunction "2_2") (pintype "passive"))
      (node (ref "C5") (pin "2") (pinfunction "2_2") (pintype "passive"))
      (node (ref "C6") (pin "1") (pinfunction "1_1") (pintype "passive"))
      (node (ref "C7") (pin "1") (pinfunction "1_1") (pintype "passive"))
      (node (ref "C8") (pin "2") (pinfunction "2_2") (pintype "passive"))
      (node (ref "C9") (pin "2") (pinfunction "2_2") (pintype "passive"))
      (node (ref "FDC_GND") (pin "TP") (pinfunction "TP_TP") (pintype "input"))
      (node (ref "FRAME-GND") (pin "TP") (pinfunction "TP_TP") (pintype "input"))
      (node (ref "GND94") (pin "TP") (pinfunction "TP_TP") (pintype "input"))
      (node (ref "GND95") (pin "TP") (pinfunction "TP_TP") (pintype "input"))
      (node (ref "GND96") (pin "TP") (pinfunction "TP_TP") (pintype "input"))
      (node (ref "GND97") (pin "TP") (pinfunction "TP_TP") (pintype "input"))
      (node (ref "GND98") (pin "TP") (pinfunction "TP_TP") (pintype "input"))
      (node (ref "GND99") (pin "TP") (pinfunction "TP_TP") (pintype "input"))
      (node (ref "INPUT-GND1") (pin "TP") (pinfunction "TP_TP") (pintype "input"))
      (node (ref "LL1") (pin "21") (pinfunction "21_21") (pintype "passive"))
      (node (ref "LL2") (pin "21") (pinfunction "21_21") (pintype "passive"))
      (node (ref "Q2") (pin "S") (pinfunction "S_S") (pintype "passive"))
      (node (ref "Q3") (pin "S") (pinfunction "S_S") (pintype "passive"))
      (node (ref "Q4") (pin "S") (pinfunction "S_S") (pintype "passive"))
      (node (ref "Q5") (pin "S") (pinfunction "S_S") (pintype "passive"))
      (node (ref "Q6") (pin "S") (pinfunction "S_S") (pintype "passive"))
      (node (ref "R1") (pin "1") (pinfunction "1_1") (pintype "passive"))
      (node (ref "R12") (pin "1") (pinfunction "1_1") (pintype "passive"))
      (node (ref "R16") (pin "2") (pinfunction "2_2") (pintype "passive"))
      (node (ref "R18") (pin "2") (pinfunction "2_2") (pintype "passive"))
      (node (ref "R20") (pin "2") (pinfunction "2_2") (pintype "passive"))
      (node (ref "R21") (pin "2") (pinfunction "2_2") (pintype "passive"))
      (node (ref "R22") (pin "2") (pinfunction "2_2") (pintype "passive"))
      (node (ref "R26") (pin "2") (pinfunction "2_2") (pintype "passive"))
      (node (ref "R3") (pin "2") (pinfunction "2_2") (pintype "passive"))
      (node (ref "R5") (pin "1") (pinfunction "1_1") (pintype "passive"))
      (node (ref "R6") (pin "1") (pinfunction "1_1") (pintype "passive"))
      (node (ref "R7") (pin "1") (pinfunction "1_1") (pintype "passive"))
      (node (ref "R8") (pin "1") (pinfunction "1_1") (pintype "passive"))
      (node (ref "U$2") (pin "15") (pinfunction "AREFIN-_15") (pintype "output"))
      (node (ref "U$2") (pin "16") (pinfunction "AGND_16") (pintype "output"))
      (node (ref "U$2") (pin "17") (pinfunction "DGND_17") (pintype "output"))
      (node (ref "UART_GND") (pin "TP") (pinfunction "TP_TP") (pintype "input"))
      (node (ref "UART_GND1") (pin "TP") (pinfunction "TP_TP") (pintype "input"))
      (node (ref "UART_GND2") (pin "TP") (pinfunction "TP_TP") (pintype "input"))
    )
    (net (code "58") (name "VCC") (class "Default")
      (node (ref "5V-INPUT") (pin "TP") (pinfunction "TP_TP") (pintype "input"))
      (node (ref "5V97") (pin "TP") (pinfunction "TP_TP") (pintype "input"))
      (node (ref "5V98") (pin "TP") (pinfunction "TP_TP") (pintype "input"))
      (node (ref "5V99") (pin "TP") (pinfunction "TP_TP") (pintype "input"))
      (node (ref "C10") (pin "1") (pinfunction "1_1") (pintype "passive"))
      (node (ref "C11") (pin "1") (pinfunction "1_1") (pintype "passive"))
      (node (ref "C12") (pin "1") (pinfunction "1_1") (pintype "passive"))
      (node (ref "C13") (pin "1") (pinfunction "1_1") (pintype "passive"))
      (node (ref "C14") (pin "1") (pinfunction "1_1") (pintype "passive"))
      (node (ref "C21") (pin "1") (pinfunction "1_1") (pintype "passive"))
      (node (ref "C22") (pin "1") (pinfunction "1_1") (pintype "passive"))
      (node (ref "C23") (pin "1") (pinfunction "1_1") (pintype "passive"))
      (node (ref "C5") (pin "1") (pinfunction "1_1") (pintype "passive"))
      (node (ref "C9") (pin "1") (pinfunction "1_1") (pintype "passive"))
      (node (ref "DISP-5V") (pin "TP") (pinfunction "TP_TP") (pintype "input"))
      (node (ref "ESP32LEFT") (pin "2") (pinfunction "2_2") (pintype "passive"))
      (node (ref "LL2") (pin "25") (pinfunction "25_25") (pintype "passive"))
      (node (ref "R13") (pin "1") (pinfunction "1_1") (pintype "passive"))
      (node (ref "SCALE1") (pin "1") (pinfunction "1_1") (pintype "passive"))
      (node (ref "SCALE2") (pin "1") (pinfunction "1_1") (pintype "passive"))
      (node (ref "SCALE3") (pin "1") (pinfunction "1_1") (pintype "passive"))
      (node (ref "SIM800L_LEFT") (pin "2") (pinfunction "2_2") (pintype "passive"))
      (node (ref "U$2") (pin "1") (pinfunction "AVDD_1") (pintype "output"))
      (node (ref "U$3") (pin "P$1") (pinfunction "1_P$1") (pintype "passive"))
      (node (ref "U$3") (pin "P$2") (pinfunction "2_P$2") (pintype "passive"))
    )
    (net (code "59") (name "unconnected-(ESP32LEFT-Pad3)") (class "Default")
      (node (ref "ESP32LEFT") (pin "3") (pinfunction "3_3") (pintype "passive"))
    )
    (net (code "60") (name "unconnected-(ESP32LEFT-Pad4)") (class "Default")
      (node (ref "ESP32LEFT") (pin "4") (pinfunction "4_4") (pintype "passive"))
    )
    (net (code "61") (name "unconnected-(ESP32LEFT-Pad7)") (class "Default")
      (node (ref "ESP32LEFT") (pin "7") (pinfunction "7_7") (pintype "passive"))
    )
    (net (code "62") (name "unconnected-(ESP32LEFT-Pad8)") (class "Default")
      (node (ref "ESP32LEFT") (pin "8") (pinfunction "8_8") (pintype "passive"))
    )
    (net (code "63") (name "unconnected-(ESP32LEFT-Pad9)") (class "Default")
      (node (ref "ESP32LEFT") (pin "9") (pinfunction "9_9") (pintype "passive"))
    )
    (net (code "64") (name "unconnected-(ESP32LEFT-Pad10)") (class "Default")
      (node (ref "ESP32LEFT") (pin "10") (pinfunction "10_10") (pintype "passive"))
    )
    (net (code "65") (name "unconnected-(ESP32LEFT-Pad11)") (class "Default")
      (node (ref "ESP32LEFT") (pin "11") (pinfunction "11_11") (pintype "passive"))
    )
    (net (code "66") (name "unconnected-(ESP32LEFT-Pad12)") (class "Default")
      (node (ref "ESP32LEFT") (pin "12") (pinfunction "12_12") (pintype "passive"))
    )
    (net (code "67") (name "unconnected-(ESP32LEFT-Pad13)") (class "Default")
      (node (ref "ESP32LEFT") (pin "13") (pinfunction "13_13") (pintype "passive"))
    )
    (net (code "68") (name "unconnected-(ESP32LEFT-Pad14)") (class "Default")
      (node (ref "ESP32LEFT") (pin "14") (pinfunction "14_14") (pintype "passive"))
    )
    (net (code "69") (name "unconnected-(ESP32LEFT-Pad15)") (class "Default")
      (node (ref "ESP32LEFT") (pin "15") (pinfunction "15_15") (pintype "passive"))
    )
    (net (code "70") (name "unconnected-(ESP32LEFT-Pad16)") (class "Default")
      (node (ref "ESP32LEFT") (pin "16") (pinfunction "16_16") (pintype "passive"))
    )
    (net (code "71") (name "unconnected-(ESPRIGHT-Pad1)") (class "Default")
      (node (ref "ESPRIGHT") (pin "1") (pinfunction "1_1") (pintype "passive"))
    )
    (net (code "72") (name "unconnected-(ESPRIGHT-Pad2)") (class "Default")
      (node (ref "ESPRIGHT") (pin "2") (pinfunction "2_2") (pintype "passive"))
    )
    (net (code "73") (name "unconnected-(ESPRIGHT-Pad3)") (class "Default")
      (node (ref "ESPRIGHT") (pin "3") (pinfunction "3_3") (pintype "passive"))
    )
    (net (code "74") (name "unconnected-(ESPRIGHT-Pad4)") (class "Default")
      (node (ref "ESPRIGHT") (pin "4") (pinfunction "4_4") (pintype "passive"))
    )
    (net (code "75") (name "unconnected-(ESPRIGHT-Pad5)") (class "Default")
      (node (ref "ESPRIGHT") (pin "5") (pinfunction "5_5") (pintype "passive"))
    )
    (net (code "76") (name "unconnected-(ESPRIGHT-Pad6)") (class "Default")
      (node (ref "ESPRIGHT") (pin "6") (pinfunction "6_6") (pintype "passive"))
    )
    (net (code "77") (name "unconnected-(ESPRIGHT-Pad7)") (class "Default")
      (node (ref "ESPRIGHT") (pin "7") (pinfunction "7_7") (pintype "passive"))
    )
    (net (code "78") (name "unconnected-(ESPRIGHT-Pad8)") (class "Default")
      (node (ref "ESPRIGHT") (pin "8") (pinfunction "8_8") (pintype "passive"))
    )
    (net (code "79") (name "unconnected-(ESPRIGHT-Pad9)") (class "Default")
      (node (ref "ESPRIGHT") (pin "9") (pinfunction "9_9") (pintype "passive"))
    )
    (net (code "80") (name "unconnected-(ESPRIGHT-Pad10)") (class "Default")
      (node (ref "ESPRIGHT") (pin "10") (pinfunction "10_10") (pintype "passive"))
    )
    (net (code "81") (name "unconnected-(ESPRIGHT-Pad11)") (class "Default")
      (node (ref "ESPRIGHT") (pin "11") (pinfunction "11_11") (pintype "passive"))
    )
    (net (code "82") (name "unconnected-(ESPRIGHT-Pad12)") (class "Default")
      (node (ref "ESPRIGHT") (pin "12") (pinfunction "12_12") (pintype "passive"))
    )
    (net (code "83") (name "unconnected-(ESPRIGHT-Pad13)") (class "Default")
      (node (ref "ESPRIGHT") (pin "13") (pinfunction "13_13") (pintype "passive"))
    )
    (net (code "84") (name "unconnected-(ESPRIGHT-Pad14)") (class "Default")
      (node (ref "ESPRIGHT") (pin "14") (pinfunction "14_14") (pintype "passive"))
    )
    (net (code "85") (name "unconnected-(ESPRIGHT-Pad15)") (class "Default")
      (node (ref "ESPRIGHT") (pin "15") (pinfunction "15_15") (pintype "passive"))
    )
    (net (code "86") (name "unconnected-(ESPRIGHT-Pad16)") (class "Default")
      (node (ref "ESPRIGHT") (pin "16") (pinfunction "16_16") (pintype "passive"))
    )
    (net (code "87") (name "unconnected-(ESPRIGHT-Pad17)") (class "Default")
      (node (ref "ESPRIGHT") (pin "17") (pinfunction "17_17") (pintype "passive"))
    )
    (net (code "88") (name "unconnected-(ESPRIGHT-Pad18)") (class "Default")
      (node (ref "ESPRIGHT") (pin "18") (pinfunction "18_18") (pintype "passive"))
    )
    (net (code "89") (name "unconnected-(LL1-Pad2)") (class "Default")
      (node (ref "LL1") (pin "2") (pinfunction "2_2") (pintype "passive"))
    )
    (net (code "90") (name "unconnected-(LL1-Pad3)") (class "Default")
      (node (ref "LL1") (pin "3") (pinfunction "3_3") (pintype "passive"))
    )
    (net (code "91") (name "unconnected-(LL1-Pad4)") (class "Default")
      (node (ref "LL1") (pin "4") (pinfunction "4_4") (pintype "passive"))
    )
    (net (code "92") (name "unconnected-(LL1-Pad5)") (class "Default")
      (node (ref "LL1") (pin "5") (pinfunction "5_5") (pintype "passive"))
    )
    (net (code "93") (name "unconnected-(LL1-Pad6)") (class "Default")
      (node (ref "LL1") (pin "6") (pinfunction "6_6") (pintype "passive"))
    )
    (net (code "94") (name "unconnected-(LL1-Pad7)") (class "Default")
      (node (ref "LL1") (pin "7") (pinfunction "7_7") (pintype "passive"))
    )
    (net (code "95") (name "unconnected-(LL1-Pad8)") (class "Default")
      (node (ref "LL1") (pin "8") (pinfunction "8_8") (pintype "passive"))
    )
    (net (code "96") (name "unconnected-(LL1-Pad9)") (class "Default")
      (node (ref "LL1") (pin "9") (pinfunction "9_9") (pintype "passive"))
    )
    (net (code "97") (name "unconnected-(LL1-Pad14)") (class "Default")
      (node (ref "LL1") (pin "14") (pinfunction "14_14") (pintype "passive"))
    )
    (net (code "98") (name "unconnected-(LL1-Pad15)") (class "Default")
      (node (ref "LL1") (pin "15") (pinfunction "15_15") (pintype "passive"))
    )
    (net (code "99") (name "unconnected-(LL1-Pad16)") (class "Default")
      (node (ref "LL1") (pin "16") (pinfunction "16_16") (pintype "passive"))
    )
    (net (code "100") (name "unconnected-(LL1-Pad18)") (class "Default")
      (node (ref "LL1") (pin "18") (pinfunction "18_18") (pintype "passive"))
    )
    (net (code "101") (name "unconnected-(LL1-Pad22)") (class "Default")
      (node (ref "LL1") (pin "22") (pinfunction "22_22") (pintype "passive"))
    )
    (net (code "102") (name "unconnected-(LL1-Pad23)") (class "Default")
      (node (ref "LL1") (pin "23") (pinfunction "23_23") (pintype "passive"))
    )
    (net (code "103") (name "unconnected-(LL1-Pad24)") (class "Default")
      (node (ref "LL1") (pin "24") (pinfunction "24_24") (pintype "passive"))
    )
    (net (code "104") (name "unconnected-(LL1-Pad25)") (class "Default")
      (node (ref "LL1") (pin "25") (pinfunction "25_25") (pintype "passive"))
    )
    (net (code "105") (name "unconnected-(LL2-Pad2)") (class "Default")
      (node (ref "LL2") (pin "2") (pinfunction "2_2") (pintype "passive"))
    )
    (net (code "106") (name "unconnected-(LL2-Pad3)") (class "Default")
      (node (ref "LL2") (pin "3") (pinfunction "3_3") (pintype "passive"))
    )
    (net (code "107") (name "unconnected-(LL2-Pad4)") (class "Default")
      (node (ref "LL2") (pin "4") (pinfunction "4_4") (pintype "passive"))
    )
    (net (code "108") (name "unconnected-(LL2-Pad5)") (class "Default")
      (node (ref "LL2") (pin "5") (pinfunction "5_5") (pintype "passive"))
    )
    (net (code "109") (name "unconnected-(LL2-Pad6)") (class "Default")
      (node (ref "LL2") (pin "6") (pinfunction "6_6") (pintype "passive"))
    )
    (net (code "110") (name "unconnected-(LL2-Pad7)") (class "Default")
      (node (ref "LL2") (pin "7") (pinfunction "7_7") (pintype "passive"))
    )
    (net (code "111") (name "unconnected-(LL2-Pad8)") (class "Default")
      (node (ref "LL2") (pin "8") (pinfunction "8_8") (pintype "passive"))
    )
    (net (code "112") (name "unconnected-(LL2-Pad9)") (class "Default")
      (node (ref "LL2") (pin "9") (pinfunction "9_9") (pintype "passive"))
    )
    (net (code "113") (name "unconnected-(LL2-Pad14)") (class "Default")
      (node (ref "LL2") (pin "14") (pinfunction "14_14") (pintype "passive"))
    )
    (net (code "114") (name "unconnected-(LL2-Pad15)") (class "Default")
      (node (ref "LL2") (pin "15") (pinfunction "15_15") (pintype "passive"))
    )
    (net (code "115") (name "unconnected-(LL2-Pad16)") (class "Default")
      (node (ref "LL2") (pin "16") (pinfunction "16_16") (pintype "passive"))
    )
    (net (code "116") (name "unconnected-(LL2-Pad18)") (class "Default")
      (node (ref "LL2") (pin "18") (pinfunction "18_18") (pintype "passive"))
    )
    (net (code "117") (name "unconnected-(LL2-Pad22)") (class "Default")
      (node (ref "LL2") (pin "22") (pinfunction "22_22") (pintype "passive"))
    )
    (net (code "118") (name "unconnected-(LL2-Pad23)") (class "Default")
      (node (ref "LL2") (pin "23") (pinfunction "23_23") (pintype "passive"))
    )
    (net (code "119") (name "unconnected-(LL2-Pad24)") (class "Default")
      (node (ref "LL2") (pin "24") (pinfunction "24_24") (pintype "passive"))
    )
    (net (code "120") (name "unconnected-(RR1-Pad2)") (class "Default")
      (node (ref "RR1") (pin "2") (pinfunction "2_2") (pintype "passive"))
    )
    (net (code "121") (name "unconnected-(RR1-Pad3)") (class "Default")
      (node (ref "RR1") (pin "3") (pinfunction "3_3") (pintype "passive"))
    )
    (net (code "122") (name "unconnected-(RR1-Pad4)") (class "Default")
      (node (ref "RR1") (pin "4") (pinfunction "4_4") (pintype "passive"))
    )
    (net (code "123") (name "unconnected-(RR1-Pad5)") (class "Default")
      (node (ref "RR1") (pin "5") (pinfunction "5_5") (pintype "passive"))
    )
    (net (code "124") (name "unconnected-(RR1-Pad6)") (class "Default")
      (node (ref "RR1") (pin "6") (pinfunction "6_6") (pintype "passive"))
    )
    (net (code "125") (name "unconnected-(RR1-Pad7)") (class "Default")
      (node (ref "RR1") (pin "7") (pinfunction "7_7") (pintype "passive"))
    )
    (net (code "126") (name "unconnected-(RR1-Pad8)") (class "Default")
      (node (ref "RR1") (pin "8") (pinfunction "8_8") (pintype "passive"))
    )
    (net (code "127") (name "unconnected-(RR1-Pad10)") (class "Default")
      (node (ref "RR1") (pin "10") (pinfunction "10_10") (pintype "passive"))
    )
    (net (code "128") (name "unconnected-(RR1-Pad11)") (class "Default")
      (node (ref "RR1") (pin "11") (pinfunction "11_11") (pintype "passive"))
    )
    (net (code "129") (name "unconnected-(RR1-Pad12)") (class "Default")
      (node (ref "RR1") (pin "12") (pinfunction "12_12") (pintype "passive"))
    )
    (net (code "130") (name "unconnected-(RR1-Pad13)") (class "Default")
      (node (ref "RR1") (pin "13") (pinfunction "13_13") (pintype "passive"))
    )
    (net (code "131") (name "unconnected-(RR1-Pad14)") (class "Default")
      (node (ref "RR1") (pin "14") (pinfunction "14_14") (pintype "passive"))
    )
    (net (code "132") (name "unconnected-(RR1-Pad15)") (class "Default")
      (node (ref "RR1") (pin "15") (pinfunction "15_15") (pintype "passive"))
    )
    (net (code "133") (name "unconnected-(RR1-Pad16)") (class "Default")
      (node (ref "RR1") (pin "16") (pinfunction "16_16") (pintype "passive"))
    )
    (net (code "134") (name "unconnected-(RR1-Pad17)") (class "Default")
      (node (ref "RR1") (pin "17") (pinfunction "17_17") (pintype "passive"))
    )
    (net (code "135") (name "unconnected-(RR1-Pad19)") (class "Default")
      (node (ref "RR1") (pin "19") (pinfunction "19_19") (pintype "passive"))
    )
    (net (code "136") (name "unconnected-(RR1-Pad21)") (class "Default")
      (node (ref "RR1") (pin "21") (pinfunction "21_21") (pintype "passive"))
    )
    (net (code "137") (name "unconnected-(RR1-Pad24)") (class "Default")
      (node (ref "RR1") (pin "24") (pinfunction "24_24") (pintype "passive"))
    )
    (net (code "138") (name "unconnected-(RR2-Pad2)") (class "Default")
      (node (ref "RR2") (pin "2") (pinfunction "2_2") (pintype "passive"))
    )
    (net (code "139") (name "unconnected-(RR2-Pad3)") (class "Default")
      (node (ref "RR2") (pin "3") (pinfunction "3_3") (pintype "passive"))
    )
    (net (code "140") (name "unconnected-(RR2-Pad4)") (class "Default")
      (node (ref "RR2") (pin "4") (pinfunction "4_4") (pintype "passive"))
    )
    (net (code "141") (name "unconnected-(RR2-Pad5)") (class "Default")
      (node (ref "RR2") (pin "5") (pinfunction "5_5") (pintype "passive"))
    )
    (net (code "142") (name "unconnected-(RR2-Pad6)") (class "Default")
      (node (ref "RR2") (pin "6") (pinfunction "6_6") (pintype "passive"))
    )
    (net (code "143") (name "unconnected-(RR2-Pad7)") (class "Default")
      (node (ref "RR2") (pin "7") (pinfunction "7_7") (pintype "passive"))
    )
    (net (code "144") (name "unconnected-(RR2-Pad8)") (class "Default")
      (node (ref "RR2") (pin "8") (pinfunction "8_8") (pintype "passive"))
    )
    (net (code "145") (name "unconnected-(RR2-Pad10)") (class "Default")
      (node (ref "RR2") (pin "10") (pinfunction "10_10") (pintype "passive"))
    )
    (net (code "146") (name "unconnected-(RR2-Pad11)") (class "Default")
      (node (ref "RR2") (pin "11") (pinfunction "11_11") (pintype "passive"))
    )
    (net (code "147") (name "unconnected-(RR2-Pad12)") (class "Default")
      (node (ref "RR2") (pin "12") (pinfunction "12_12") (pintype "passive"))
    )
    (net (code "148") (name "unconnected-(RR2-Pad13)") (class "Default")
      (node (ref "RR2") (pin "13") (pinfunction "13_13") (pintype "passive"))
    )
    (net (code "149") (name "unconnected-(RR2-Pad14)") (class "Default")
      (node (ref "RR2") (pin "14") (pinfunction "14_14") (pintype "passive"))
    )
    (net (code "150") (name "unconnected-(RR2-Pad15)") (class "Default")
      (node (ref "RR2") (pin "15") (pinfunction "15_15") (pintype "passive"))
    )
    (net (code "151") (name "unconnected-(RR2-Pad16)") (class "Default")
      (node (ref "RR2") (pin "16") (pinfunction "16_16") (pintype "passive"))
    )
    (net (code "152") (name "unconnected-(RR2-Pad17)") (class "Default")
      (node (ref "RR2") (pin "17") (pinfunction "17_17") (pintype "passive"))
    )
    (net (code "153") (name "unconnected-(RR2-Pad21)") (class "Default")
      (node (ref "RR2") (pin "21") (pinfunction "21_21") (pintype "passive"))
    )
    (net (code "154") (name "unconnected-(RR2-Pad24)") (class "Default")
      (node (ref "RR2") (pin "24") (pinfunction "24_24") (pintype "passive"))
    )
    (net (code "155") (name "unconnected-(SIM800L_LEFT-Pad1)") (class "Default")
      (node (ref "SIM800L_LEFT") (pin "1") (pinfunction "1_1") (pintype "passive"))
    )
    (net (code "156") (name "unconnected-(SIM800L_LEFT-Pad3)") (class "Default")
      (node (ref "SIM800L_LEFT") (pin "3") (pinfunction "3_3") (pintype "passive"))
    )
    (net (code "157") (name "unconnected-(SIM800_RIGHT-Pad1)") (class "Default")
      (node (ref "SIM800_RIGHT") (pin "1") (pinfunction "1_1") (pintype "passive"))
    )
    (net (code "158") (name "unconnected-(SIM800_RIGHT-Pad2)") (class "Default")
      (node (ref "SIM800_RIGHT") (pin "2") (pinfunction "2_2") (pintype "passive"))
    )
    (net (code "159") (name "unconnected-(SIM800_RIGHT-Pad3)") (class "Default")
      (node (ref "SIM800_RIGHT") (pin "3") (pinfunction "3_3") (pintype "passive"))
    )
    (net (code "160") (name "unconnected-(SIM800_RIGHT-Pad4)") (class "Default")
      (node (ref "SIM800_RIGHT") (pin "4") (pinfunction "4_4") (pintype "passive"))
    )
    (net (code "161") (name "unconnected-(SIM800_RIGHT-Pad5)") (class "Default")
      (node (ref "SIM800_RIGHT") (pin "5") (pinfunction "5_5") (pintype "passive"))
    )
    (net (code "162") (name "unconnected-(SIM800_RIGHT-Pad6)") (class "Default")
      (node (ref "SIM800_RIGHT") (pin "6") (pinfunction "6_6") (pintype "passive"))
    )
    (net (code "163") (name "unconnected-(U$1-CIN3-Pad4)") (class "Default")
      (node (ref "U$1") (pin "4") (pinfunction "CIN3_4") (pintype "input"))
    )
    (net (code "164") (name "unconnected-(U$1-CIN4-Pad5)") (class "Default")
      (node (ref "U$1") (pin "5") (pinfunction "CIN4_5") (pintype "input"))
    )
    (net (code "165") (name "unconnected-(U$1-SHLD2-Pad6)") (class "Default")
      (node (ref "U$1") (pin "6") (pinfunction "SHLD2_6") (pintype "output"))
    )
    (net (code "166") (name "unconnected-(U$2-CRA-Pad18)") (class "Default")
      (node (ref "U$2") (pin "18") (pinfunction "CRA_18") (pintype "output"))
    )
    (net (code "167") (name "unconnected-(U$2-DRB-Pad19)") (class "Default")
      (node (ref "U$2") (pin "19") (pinfunction "DRB_19") (pintype "output"))
    )
    (net (code "168") (name "unconnected-(U$2-DRC-Pad20)") (class "Default")
      (node (ref "U$2") (pin "20") (pinfunction "DRC_20") (pintype "output"))
    )
  )
)
